# FLASHSPI_M25PX0.net
KiCad netlist of a schematic drawn in Altium Designer
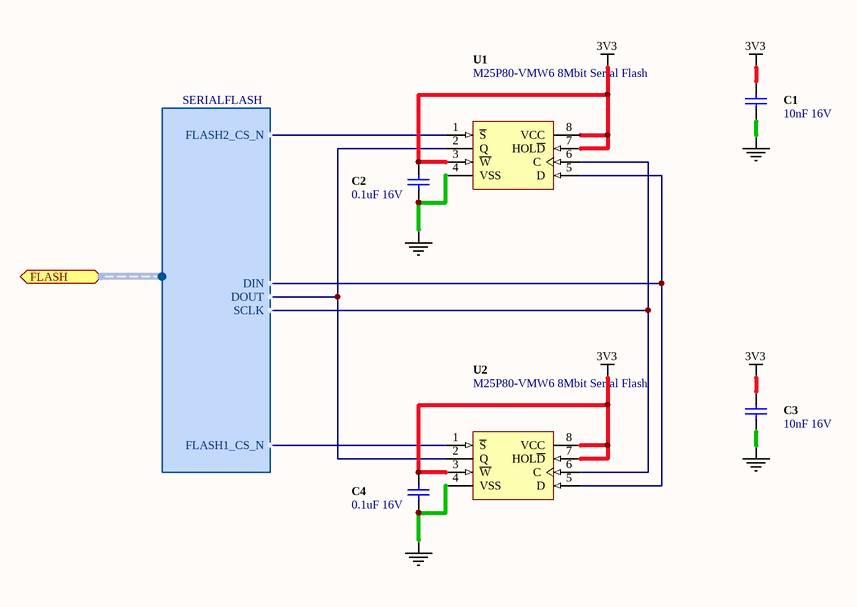
[diagram p0: FLASHSPI_M25PX0.SchDoc]

(export (version "E")
  (design (tool "Eeschema 10.0.6"))
  (components
    (comp (ref "C1")
      (value "10nF 16V")
      (footprint "CAPC1005-STAR")
      (description "Capacitor, Ceramic, 10nF 10% 16V 0402 (1005) X7R")
      (fields (field (name "TOLERANCE") "10 %"))
      (libsource (lib "altium-import") (part "root_0_CAP-NP_"))
    )
    (comp (ref "C2")
      (value "0.1uF 16V")
      (footprint "CAPC1005-STAR")
      (description "Capacitor, Ceramic, 0.1uF 10% 16V 0402 (1005) X7R")
      (fields (field (name "TOLERANCE") "10 %"))
      (libsource (lib "altium-import") (part "root_2_CAP-NP_"))
    )
    (comp (ref "C3")
      (value "10nF 16V")
      (footprint "CAPC1005-STAR")
      (description "Capacitor, Ceramic, 10nF 10% 16V 0402 (1005) X7R")
      (fields (field (name "TOLERANCE") "10 %"))
      (libsource (lib "altium-import") (part "root_0_CAP-NP_"))
    )
    (comp (ref "C4")
      (value "0.1uF 16V")
      (footprint "CAPC1005-STAR")
      (description "Capacitor, Ceramic, 0.1uF 10% 16V 0402 (1005) X7R")
      (fields (field (name "TOLERANCE") "10 %"))
      (libsource (lib "altium-import") (part "root_2_CAP-NP_"))
    )
    (comp (ref "U1")
      (value "M25P80-VMW6 8Mbit Serial Flash")
      (footprint "SOIC8-200-BODY")
      (libsource (lib "altium-import") (part "root_0_M25P80_"))
    )
    (comp (ref "U2")
      (value "M25P80-VMW6 8Mbit Serial Flash")
      (footprint "SOIC8-200-BODY")
      (libsource (lib "altium-import") (part "root_0_M25P80_"))
    )
  )
  (nets
    (net (code "2") (name "/DIN") (class "Default")
      (node (ref "U1") (pin "5") (pinfunction "D_5") (pintype "input"))
      (node (ref "U2") (pin "5") (pinfunction "D_5") (pintype "input"))
    )
    (net (code "3") (name "/DOUT") (class "Default")
      (node (ref "U1") (pin "2") (pinfunction "Q_2") (pintype "tri_state"))
      (node (ref "U2") (pin "2") (pinfunction "Q_2") (pintype "tri_state"))
    )
    (net (code "4") (name "/FLASH1_CS_N") (class "Default")
      (node (ref "U2") (pin "1") (pinfunction "~{S}_1") (pintype "input"))
    )
    (net (code "5") (name "/FLASH2_CS_N") (class "Default")
      (node (ref "U1") (pin "1") (pinfunction "~{S}_1") (pintype "input"))
    )
    (net (code "6") (name "/SCLK") (class "Default")
      (node (ref "U1") (pin "6") (pinfunction "C_6") (pintype "input"))
      (node (ref "U2") (pin "6") (pinfunction "C_6") (pintype "input"))
    )
    (net (code "8") (name "3V3") (class "Default")
      (node (ref "C1") (pin "1") (pinfunction "1_1") (pintype "passive"))
      (node (ref "C2") (pin "2") (pinfunction "2_2") (pintype "passive"))
      (node (ref "C3") (pin "1") (pinfunction "1_1") (pintype "passive"))
      (node (ref "C4") (pin "2") (pinfunction "2_2") (pintype "passive"))
      (node (ref "U1") (pin "3") (pinfunction "~{W}_3") (pintype "input"))
      (node (ref "U1") (pin "7") (pinfunction "HOL~{D}_7") (pintype "input"))
      (node (ref "U1") (pin "8") (pinfunction "VCC_8") (pintype "power_in"))
      (node (ref "U2") (pin "3") (pinfunction "~{W}_3") (pintype "input"))
      (node (ref "U2") (pin "7") (pinfunction "HOL~{D}_7") (pintype "input"))
      (node (ref "U2") (pin "8") (pinfunction "VCC_8") (pintype "power_in"))
    )
    (net (code "9") (name "GND") (class "Default")
      (node (ref "C1") (pin "2") (pinfunction "2_2") (pintype "passive"))
      (node (ref "C2") (pin "1") (pinfunction "1_1") (pintype "passive"))
      (node (ref "C3") (pin "2") (pinfunction "2_2") (pintype "passive"))
      (node (ref "C4") (pin "1") (pinfunction "1_1") (pintype "passive"))
      (node (ref "U1") (pin "4") (pinfunction "VSS_4") (pintype "power_in"))
      (node (ref "U2") (pin "4") (pinfunction "VSS_4") (pintype "power_in"))
    )
  )
)
